# G021K.net
KiCad netlist of a schematic drawn in EAGLE
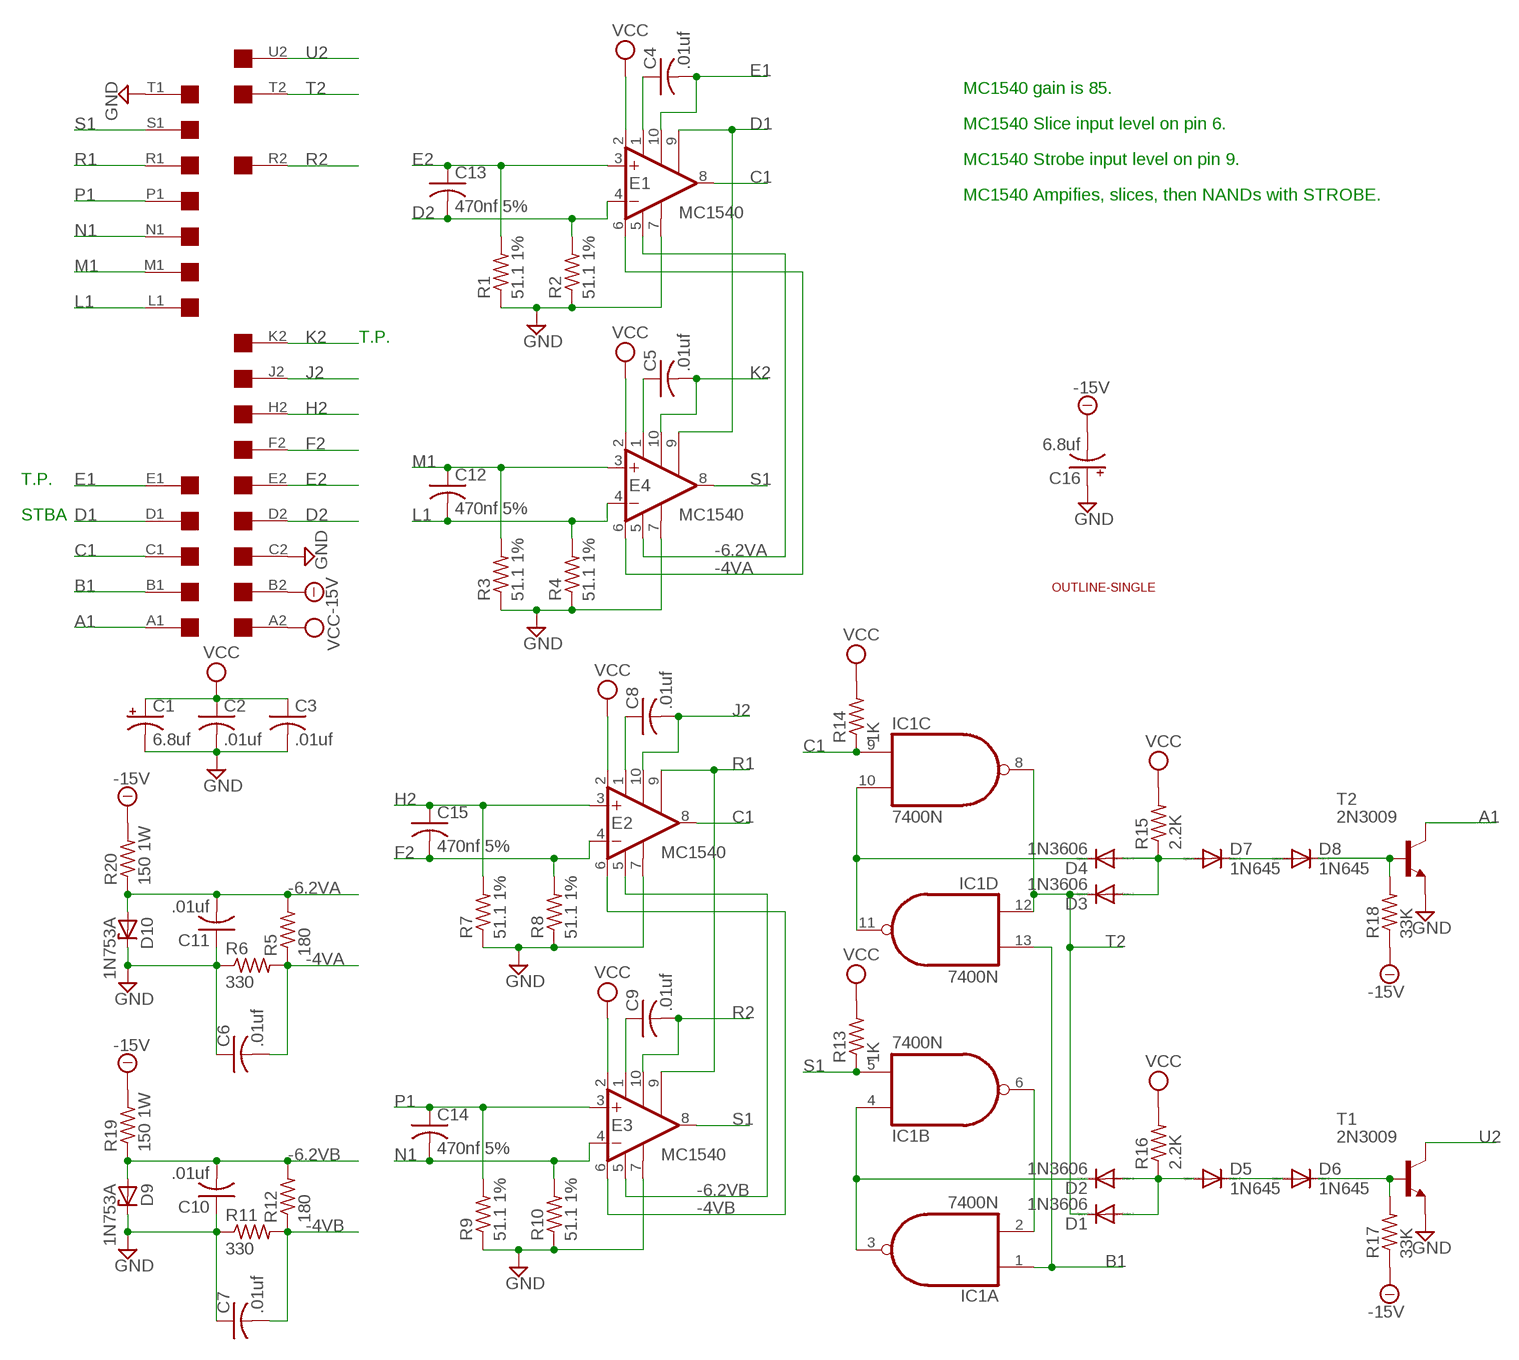
[diagram p0: schematic, sheet 1]

(export (version "E")
  (design (tool "Eeschema 10.0.6"))
  (components
    (comp (ref "C1")
      (value "6.8uf")
      (footprint "eagle-import:E22-6")
      (libsource (lib "eagle-import") (part "CPOL-USE22-6AXIAL"))
    )
    (comp (ref "C2")
      (value ".01uf")
      (footprint "eagle-import:C050-025X075")
      (libsource (lib "eagle-import") (part "C-US050-025X075"))
    )
    (comp (ref "C3")
      (value ".01uf")
      (footprint "eagle-import:C050-025X075")
      (libsource (lib "eagle-import") (part "C-US050-025X075"))
    )
    (comp (ref "C4")
      (value ".01uf")
      (footprint "eagle-import:C050-025X075")
      (libsource (lib "eagle-import") (part "C-US050-025X075"))
    )
    (comp (ref "C5")
      (value ".01uf")
      (footprint "eagle-import:C050-025X075")
      (libsource (lib "eagle-import") (part "C-US050-025X075"))
    )
    (comp (ref "C6")
      (value ".01uf")
      (footprint "eagle-import:C050-025X075")
      (libsource (lib "eagle-import") (part "C-US050-025X075"))
    )
    (comp (ref "C7")
      (value ".01uf")
      (footprint "eagle-import:C050-025X075")
      (libsource (lib "eagle-import") (part "C-US050-025X075"))
    )
    (comp (ref "C8")
      (value ".01uf")
      (footprint "eagle-import:C050-025X075")
      (libsource (lib "eagle-import") (part "C-US050-025X075"))
    )
    (comp (ref "C9")
      (value ".01uf")
      (footprint "eagle-import:C050-025X075")
      (libsource (lib "eagle-import") (part "C-US050-025X075"))
    )
    (comp (ref "C10")
      (value ".01uf")
      (footprint "eagle-import:C050-025X075")
      (libsource (lib "eagle-import") (part "C-US050-025X075"))
    )
    (comp (ref "C11")
      (value ".01uf")
      (footprint "eagle-import:C050-025X075")
      (libsource (lib "eagle-import") (part "C-US050-025X075"))
    )
    (comp (ref "C12")
      (value "470nf 5%")
      (footprint "eagle-import:C050-025X075")
      (libsource (lib "eagle-import") (part "C-US050-025X075"))
    )
    (comp (ref "C13")
      (value "470nf 5%")
      (footprint "eagle-import:C050-025X075")
      (libsource (lib "eagle-import") (part "C-US050-025X075"))
    )
    (comp (ref "C14")
      (value "470nf 5%")
      (footprint "eagle-import:C050-025X075")
      (libsource (lib "eagle-import") (part "C-US050-025X075"))
    )
    (comp (ref "C15")
      (value "470nf 5%")
      (footprint "eagle-import:C050-025X075")
      (libsource (lib "eagle-import") (part "C-US050-025X075"))
    )
    (comp (ref "C16")
      (value "6.8uf")
      (footprint "eagle-import:E22-6")
      (libsource (lib "eagle-import") (part "CPOL-USE22-6AXIAL"))
    )
    (comp (ref "D1")
      (value "1N3606")
      (footprint "eagle-import:DO35-10")
      (libsource (lib "eagle-import") (part "1N4148DO35-10"))
    )
    (comp (ref "D2")
      (value "1N3606")
      (footprint "eagle-import:DO35-10")
      (libsource (lib "eagle-import") (part "1N4148DO35-10"))
    )
    (comp (ref "D3")
      (value "1N3606")
      (footprint "eagle-import:DO35-10")
      (libsource (lib "eagle-import") (part "1N4148DO35-10"))
    )
    (comp (ref "D4")
      (value "1N3606")
      (footprint "eagle-import:DO35-10")
      (libsource (lib "eagle-import") (part "1N4148DO35-10"))
    )
    (comp (ref "D5")
      (value "1N645")
      (footprint "eagle-import:DO35-10")
      (libsource (lib "eagle-import") (part "1N4148DO35-10"))
    )
    (comp (ref "D6")
      (value "1N645")
      (footprint "eagle-import:DO35-10")
      (libsource (lib "eagle-import") (part "1N4148DO35-10"))
    )
    (comp (ref "D7")
      (value "1N645")
      (footprint "eagle-import:DO35-10")
      (libsource (lib "eagle-import") (part "1N4148DO35-10"))
    )
    (comp (ref "D8")
      (value "1N645")
      (footprint "eagle-import:DO35-10")
      (libsource (lib "eagle-import") (part "1N4148DO35-10"))
    )
    (comp (ref "D9")
      (value "1N753A")
      (footprint "eagle-import:F126Z10")
      (libsource (lib "eagle-import") (part "ZENER-DIODEF126-10"))
    )
    (comp (ref "D10")
      (value "1N753A")
      (footprint "eagle-import:F126Z10")
      (libsource (lib "eagle-import") (part "ZENER-DIODEF126-10"))
    )
    (comp (ref "E1")
      (value "MC1540")
      (footprint "eagle-import:602B")
      (libsource (lib "eagle-import") (part "MC1540G"))
    )
    (comp (ref "E2")
      (value "MC1540")
      (footprint "eagle-import:602B")
      (libsource (lib "eagle-import") (part "MC1540G"))
    )
    (comp (ref "E3")
      (value "MC1540")
      (footprint "eagle-import:602B")
      (libsource (lib "eagle-import") (part "MC1540G"))
    )
    (comp (ref "E4")
      (value "MC1540")
      (footprint "eagle-import:602B")
      (libsource (lib "eagle-import") (part "MC1540G"))
    )
    (comp (ref "IC1")
      (value "7400N")
      (footprint "eagle-import:DIL14")
      (libsource (lib "eagle-import") (part "7400N"))
    )
    (comp (ref "R1")
      (value "51.1 1%")
      (footprint "eagle-import:0207_10")
      (libsource (lib "eagle-import") (part "R-US_0207/10"))
    )
    (comp (ref "R2")
      (value "51.1 1%")
      (footprint "eagle-import:0207_10")
      (libsource (lib "eagle-import") (part "R-US_0207/10"))
    )
    (comp (ref "R3")
      (value "51.1 1%")
      (footprint "eagle-import:0207_10")
      (libsource (lib "eagle-import") (part "R-US_0207/10"))
    )
    (comp (ref "R4")
      (value "51.1 1%")
      (footprint "eagle-import:0207_10")
      (libsource (lib "eagle-import") (part "R-US_0207/10"))
    )
    (comp (ref "R5")
      (value "180")
      (footprint "eagle-import:0207_10")
      (libsource (lib "eagle-import") (part "R-US_0207/10"))
    )
    (comp (ref "R6")
      (value "330")
      (footprint "eagle-import:0207_10")
      (libsource (lib "eagle-import") (part "R-US_0207/10"))
    )
    (comp (ref "R7")
      (value "51.1 1%")
      (footprint "eagle-import:0207_10")
      (libsource (lib "eagle-import") (part "R-US_0207/10"))
    )
    (comp (ref "R8")
      (value "51.1 1%")
      (footprint "eagle-import:0207_10")
      (libsource (lib "eagle-import") (part "R-US_0207/10"))
    )
    (comp (ref "R9")
      (value "51.1 1%")
      (footprint "eagle-import:0207_10")
      (libsource (lib "eagle-import") (part "R-US_0207/10"))
    )
    (comp (ref "R10")
      (value "51.1 1%")
      (footprint "eagle-import:0207_10")
      (libsource (lib "eagle-import") (part "R-US_0207/10"))
    )
    (comp (ref "R11")
      (value "330")
      (footprint "eagle-import:0207_10")
      (libsource (lib "eagle-import") (part "R-US_0207/10"))
    )
    (comp (ref "R12")
      (value "180")
      (footprint "eagle-import:0207_10")
      (libsource (lib "eagle-import") (part "R-US_0207/10"))
    )
    (comp (ref "R13")
      (value "1K")
      (footprint "eagle-import:0207_10")
      (libsource (lib "eagle-import") (part "R-US_0207/10"))
    )
    (comp (ref "R14")
      (value "1K")
      (footprint "eagle-import:0207_10")
      (libsource (lib "eagle-import") (part "R-US_0207/10"))
    )
    (comp (ref "R15")
      (value "2.2K")
      (footprint "eagle-import:0207_10")
      (libsource (lib "eagle-import") (part "R-US_0207/10"))
    )
    (comp (ref "R16")
      (value "2.2K")
      (footprint "eagle-import:0207_10")
      (libsource (lib "eagle-import") (part "R-US_0207/10"))
    )
    (comp (ref "R17")
      (value "33K")
      (footprint "eagle-import:0207_10")
      (libsource (lib "eagle-import") (part "R-US_0207/10"))
    )
    (comp (ref "R18")
      (value "33K")
      (footprint "eagle-import:0207_10")
      (libsource (lib "eagle-import") (part "R-US_0207/10"))
    )
    (comp (ref "R19")
      (value "150 1W")
      (footprint "eagle-import:0414_15")
      (libsource (lib "eagle-import") (part "R-US_0414/15"))
    )
    (comp (ref "R20")
      (value "150 1W")
      (footprint "eagle-import:0414_15")
      (libsource (lib "eagle-import") (part "R-US_0414/15"))
    )
    (comp (ref "T1")
      (value "2N3009")
      (footprint "eagle-import:TO92")
      (libsource (lib "eagle-import") (part "2N3565"))
    )
    (comp (ref "T2")
      (value "2N3009")
      (footprint "eagle-import:TO92")
      (libsource (lib "eagle-import") (part "2N3565"))
    )
    (comp (ref "U$1")
      (value "SINGLE")
      (footprint "eagle-import:EDGE-CON2")
      (libsource (lib "eagle-import") (part "SINGLE"))
    )
    (comp (ref "U$2")
      (value "OUTLINE-SINGLE")
      (footprint "eagle-import:SINGLE")
      (libsource (lib "eagle-import") (part "OUTLINE-SINGLE"))
    )
  )
  (nets
    (net (code "1") (name "-15V") (class "Default")
      (node (ref "C16") (pin "-") (pinfunction "-_-") (pintype "passive"))
      (node (ref "R17") (pin "1") (pinfunction "1_1") (pintype "passive"))
      (node (ref "R18") (pin "1") (pinfunction "1_1") (pintype "passive"))
      (node (ref "R19") (pin "2") (pinfunction "2_2") (pintype "passive"))
      (node (ref "R20") (pin "2") (pinfunction "2_2") (pintype "passive"))
      (node (ref "U$1") (pin "B2") (pinfunction "1_B2") (pintype "bidirectional"))
    )
    (net (code "2") (name "/-4VA") (class "Default")
      (node (ref "C6") (pin "2") (pinfunction "2_2") (pintype "passive"))
      (node (ref "E1") (pin "6") (pinfunction "SLICE_6") (pintype "bidirectional"))
      (node (ref "E4") (pin "6") (pinfunction "SLICE_6") (pintype "bidirectional"))
      (node (ref "R5") (pin "1") (pinfunction "1_1") (pintype "passive"))
      (node (ref "R6") (pin "2") (pinfunction "2_2") (pintype "passive"))
    )
    (net (code "3") (name "/-4VB") (class "Default")
      (node (ref "C7") (pin "2") (pinfunction "2_2") (pintype "passive"))
      (node (ref "E2") (pin "6") (pinfunction "SLICE_6") (pintype "bidirectional"))
      (node (ref "E3") (pin "6") (pinfunction "SLICE_6") (pintype "bidirectional"))
      (node (ref "R11") (pin "2") (pinfunction "2_2") (pintype "passive"))
      (node (ref "R12") (pin "1") (pinfunction "1_1") (pintype "passive"))
    )
    (net (code "4") (name "/-6.2VA") (class "Default")
      (node (ref "C11") (pin "2") (pinfunction "2_2") (pintype "passive"))
      (node (ref "D10") (pin "A") (pinfunction "A_A") (pintype "passive"))
      (node (ref "E1") (pin "5") (pinfunction "V-_5") (pintype "power_in"))
      (node (ref "E4") (pin "5") (pinfunction "V-_5") (pintype "power_in"))
      (node (ref "R20") (pin "1") (pinfunction "1_1") (pintype "passive"))
      (node (ref "R5") (pin "2") (pinfunction "2_2") (pintype "passive"))
    )
    (net (code "5") (name "/-6.2VB") (class "Default")
      (node (ref "C10") (pin "2") (pinfunction "2_2") (pintype "passive"))
      (node (ref "D9") (pin "A") (pinfunction "A_A") (pintype "passive"))
      (node (ref "E2") (pin "5") (pinfunction "V-_5") (pintype "power_in"))
      (node (ref "E3") (pin "5") (pinfunction "V-_5") (pintype "power_in"))
      (node (ref "R12") (pin "2") (pinfunction "2_2") (pintype "passive"))
      (node (ref "R19") (pin "1") (pinfunction "1_1") (pintype "passive"))
    )
    (net (code "6") (name "/A1") (class "Default")
      (node (ref "T2") (pin "1") (pinfunction "C_1") (pintype "passive"))
      (node (ref "U$1") (pin "A1") (pinfunction "1_A1") (pintype "bidirectional"))
    )
    (net (code "7") (name "/B1") (class "Default")
      (node (ref "IC1") (pin "1") (pinfunction "I0_1") (pintype "input"))
      (node (ref "IC1") (pin "13") (pinfunction "I1_13") (pintype "input"))
      (node (ref "U$1") (pin "B1") (pinfunction "1_B1") (pintype "bidirectional"))
    )
    (net (code "8") (name "/C1") (class "Default")
      (node (ref "E1") (pin "8") (pinfunction "OUT_8") (pintype "open_collector"))
      (node (ref "E2") (pin "8") (pinfunction "OUT_8") (pintype "open_collector"))
      (node (ref "IC1") (pin "9") (pinfunction "I0_9") (pintype "input"))
      (node (ref "R14") (pin "1") (pinfunction "1_1") (pintype "passive"))
      (node (ref "U$1") (pin "C1") (pinfunction "1_C1") (pintype "bidirectional"))
    )
    (net (code "9") (name "/D1") (class "Default")
      (node (ref "E1") (pin "9") (pinfunction "ISTROBE_9") (pintype "passive"))
      (node (ref "E4") (pin "9") (pinfunction "ISTROBE_9") (pintype "passive"))
      (node (ref "U$1") (pin "D1") (pinfunction "1_D1") (pintype "bidirectional"))
    )
    (net (code "10") (name "/D2") (class "Default")
      (node (ref "C13") (pin "2") (pinfunction "2_2") (pintype "passive"))
      (node (ref "E1") (pin "4") (pinfunction "-IN_4") (pintype "input"))
      (node (ref "R2") (pin "2") (pinfunction "2_2") (pintype "passive"))
      (node (ref "U$1") (pin "D2") (pinfunction "1_D2") (pintype "bidirectional"))
    )
    (net (code "11") (name "/E1") (class "Default")
      (node (ref "C4") (pin "2") (pinfunction "2_2") (pintype "passive"))
      (node (ref "E1") (pin "10") (pinfunction "CEXTB_10") (pintype "passive"))
      (node (ref "U$1") (pin "E1") (pinfunction "1_E1") (pintype "bidirectional"))
    )
    (net (code "12") (name "/E2") (class "Default")
      (node (ref "C13") (pin "1") (pinfunction "1_1") (pintype "passive"))
      (node (ref "E1") (pin "3") (pinfunction "+IN_3") (pintype "input"))
      (node (ref "R1") (pin "2") (pinfunction "2_2") (pintype "passive"))
      (node (ref "U$1") (pin "E2") (pinfunction "1_E2") (pintype "bidirectional"))
    )
    (net (code "13") (name "/F2") (class "Default")
      (node (ref "C15") (pin "2") (pinfunction "2_2") (pintype "passive"))
      (node (ref "E2") (pin "4") (pinfunction "-IN_4") (pintype "input"))
      (node (ref "R8") (pin "2") (pinfunction "2_2") (pintype "passive"))
      (node (ref "U$1") (pin "F2") (pinfunction "1_F2") (pintype "bidirectional"))
    )
    (net (code "14") (name "/H2") (class "Default")
      (node (ref "C15") (pin "1") (pinfunction "1_1") (pintype "passive"))
      (node (ref "E2") (pin "3") (pinfunction "+IN_3") (pintype "input"))
      (node (ref "R7") (pin "2") (pinfunction "2_2") (pintype "passive"))
      (node (ref "U$1") (pin "H2") (pinfunction "1_H2") (pintype "bidirectional"))
    )
    (net (code "15") (name "/J2") (class "Default")
      (node (ref "C8") (pin "2") (pinfunction "2_2") (pintype "passive"))
      (node (ref "E2") (pin "10") (pinfunction "CEXTB_10") (pintype "passive"))
      (node (ref "U$1") (pin "J2") (pinfunction "1_J2") (pintype "bidirectional"))
    )
    (net (code "16") (name "/K2") (class "Default")
      (node (ref "C5") (pin "2") (pinfunction "2_2") (pintype "passive"))
      (node (ref "E4") (pin "10") (pinfunction "CEXTB_10") (pintype "passive"))
      (node (ref "U$1") (pin "K2") (pinfunction "1_K2") (pintype "bidirectional"))
    )
    (net (code "17") (name "/L1") (class "Default")
      (node (ref "C12") (pin "2") (pinfunction "2_2") (pintype "passive"))
      (node (ref "E4") (pin "4") (pinfunction "-IN_4") (pintype "input"))
      (node (ref "R4") (pin "2") (pinfunction "2_2") (pintype "passive"))
      (node (ref "U$1") (pin "L1") (pinfunction "1_L1") (pintype "bidirectional"))
    )
    (net (code "18") (name "/M1") (class "Default")
      (node (ref "C12") (pin "1") (pinfunction "1_1") (pintype "passive"))
      (node (ref "E4") (pin "3") (pinfunction "+IN_3") (pintype "input"))
      (node (ref "R3") (pin "2") (pinfunction "2_2") (pintype "passive"))
      (node (ref "U$1") (pin "M1") (pinfunction "1_M1") (pintype "bidirectional"))
    )
    (net (code "19") (name "/N1") (class "Default")
      (node (ref "C14") (pin "2") (pinfunction "2_2") (pintype "passive"))
      (node (ref "E3") (pin "4") (pinfunction "-IN_4") (pintype "input"))
      (node (ref "R10") (pin "2") (pinfunction "2_2") (pintype "passive"))
      (node (ref "U$1") (pin "N1") (pinfunction "1_N1") (pintype "bidirectional"))
    )
    (net (code "20") (name "/P1") (class "Default")
      (node (ref "C14") (pin "1") (pinfunction "1_1") (pintype "passive"))
      (node (ref "E3") (pin "3") (pinfunction "+IN_3") (pintype "input"))
      (node (ref "R9") (pin "2") (pinfunction "2_2") (pintype "passive"))
      (node (ref "U$1") (pin "P1") (pinfunction "1_P1") (pintype "bidirectional"))
    )
    (net (code "21") (name "/R1") (class "Default")
      (node (ref "E2") (pin "9") (pinfunction "ISTROBE_9") (pintype "passive"))
      (node (ref "E3") (pin "9") (pinfunction "ISTROBE_9") (pintype "passive"))
      (node (ref "U$1") (pin "R1") (pinfunction "1_R1") (pintype "bidirectional"))
    )
    (net (code "22") (name "/R2") (class "Default")
      (node (ref "C9") (pin "2") (pinfunction "2_2") (pintype "passive"))
      (node (ref "E3") (pin "10") (pinfunction "CEXTB_10") (pintype "passive"))
      (node (ref "U$1") (pin "R2") (pinfunction "1_R2") (pintype "bidirectional"))
    )
    (net (code "23") (name "/S1") (class "Default")
      (node (ref "E3") (pin "8") (pinfunction "OUT_8") (pintype "open_collector"))
      (node (ref "E4") (pin "8") (pinfunction "OUT_8") (pintype "open_collector"))
      (node (ref "IC1") (pin "5") (pinfunction "I1_5") (pintype "input"))
      (node (ref "R13") (pin "1") (pinfunction "1_1") (pintype "passive"))
      (node (ref "U$1") (pin "S1") (pinfunction "1_S1") (pintype "bidirectional"))
    )
    (net (code "24") (name "/T2") (class "Default")
      (node (ref "D1") (pin "C") (pinfunction "C_C") (pintype "passive"))
      (node (ref "D3") (pin "C") (pinfunction "C_C") (pintype "passive"))
      (node (ref "IC1") (pin "12") (pinfunction "I0_12") (pintype "input"))
      (node (ref "IC1") (pin "8") (pinfunction "O_8") (pintype "output"))
      (node (ref "U$1") (pin "T2") (pinfunction "1_T2") (pintype "bidirectional"))
    )
    (net (code "25") (name "/U2") (class "Default")
      (node (ref "T1") (pin "1") (pinfunction "C_1") (pintype "passive"))
      (node (ref "U$1") (pin "U2") (pinfunction "1_U2") (pintype "bidirectional"))
    )
    (net (code "26") (name "GND") (class "Default")
      (node (ref "C1") (pin "-") (pinfunction "-_-") (pintype "passive"))
      (node (ref "C10") (pin "1") (pinfunction "1_1") (pintype "passive"))
      (node (ref "C11") (pin "1") (pinfunction "1_1") (pintype "passive"))
      (node (ref "C16") (pin "+") (pinfunction "+_+") (pintype "passive"))
      (node (ref "C2") (pin "2") (pinfunction "2_2") (pintype "passive"))
      (node (ref "C3") (pin "2") (pinfunction "2_2") (pintype "passive"))
      (node (ref "C6") (pin "1") (pinfunction "1_1") (pintype "passive"))
      (node (ref "C7") (pin "1") (pinfunction "1_1") (pintype "passive"))
      (node (ref "D10") (pin "C") (pinfunction "C_C") (pintype "passive"))
      (node (ref "D9") (pin "C") (pinfunction "C_C") (pintype "passive"))
      (node (ref "E1") (pin "7") (pinfunction "GND_7") (pintype "power_in"))
      (node (ref "E2") (pin "7") (pinfunction "GND_7") (pintype "power_in"))
      (node (ref "E3") (pin "7") (pinfunction "GND_7") (pintype "power_in"))
      (node (ref "E4") (pin "7") (pinfunction "GND_7") (pintype "power_in"))
      (node (ref "R1") (pin "1") (pinfunction "1_1") (pintype "passive"))
      (node (ref "R10") (pin "1") (pinfunction "1_1") (pintype "passive"))
      (node (ref "R11") (pin "1") (pinfunction "1_1") (pintype "passive"))
      (node (ref "R2") (pin "1") (pinfunction "1_1") (pintype "passive"))
      (node (ref "R3") (pin "1") (pinfunction "1_1") (pintype "passive"))
      (node (ref "R4") (pin "1") (pinfunction "1_1") (pintype "passive"))
      (node (ref "R6") (pin "1") (pinfunction "1_1") (pintype "passive"))
      (node (ref "R7") (pin "1") (pinfunction "1_1") (pintype "passive"))
      (node (ref "R8") (pin "1") (pinfunction "1_1") (pintype "passive"))
      (node (ref "R9") (pin "1") (pinfunction "1_1") (pintype "passive"))
      (node (ref "T1") (pin "3") (pinfunction "E_3") (pintype "passive"))
      (node (ref "T2") (pin "3") (pinfunction "E_3") (pintype "passive"))
      (node (ref "U$1") (pin "C2") (pinfunction "1_C2") (pintype "bidirectional"))
      (node (ref "U$1") (pin "T1") (pinfunction "1_T1") (pintype "bidirectional"))
    )
    (net (code "27") (name "Net-(D1-PadA)") (class "Default")
      (node (ref "D1") (pin "A") (pinfunction "A_A") (pintype "passive"))
      (node (ref "D2") (pin "A") (pinfunction "A_A") (pintype "passive"))
      (node (ref "D5") (pin "A") (pinfunction "A_A") (pintype "passive"))
      (node (ref "R16") (pin "1") (pinfunction "1_1") (pintype "passive"))
    )
    (net (code "28") (name "Net-(D3-PadA)") (class "Default")
      (node (ref "D3") (pin "A") (pinfunction "A_A") (pintype "passive"))
      (node (ref "D4") (pin "A") (pinfunction "A_A") (pintype "passive"))
      (node (ref "D7") (pin "A") (pinfunction "A_A") (pintype "passive"))
      (node (ref "R15") (pin "1") (pinfunction "1_1") (pintype "passive"))
    )
    (net (code "29") (name "Net-(D5-PadC)") (class "Default")
      (node (ref "D5") (pin "C") (pinfunction "C_C") (pintype "passive"))
      (node (ref "D6") (pin "A") (pinfunction "A_A") (pintype "passive"))
    )
    (net (code "30") (name "Net-(D7-PadC)") (class "Default")
      (node (ref "D7") (pin "C") (pinfunction "C_C") (pintype "passive"))
      (node (ref "D8") (pin "A") (pinfunction "A_A") (pintype "passive"))
    )
    (net (code "31") (name "Net-(E1-CEXTA)") (class "Default")
      (node (ref "C4") (pin "1") (pinfunction "1_1") (pintype "passive"))
      (node (ref "E1") (pin "1") (pinfunction "CEXTA_1") (pintype "passive"))
    )
    (net (code "32") (name "Net-(E2-CEXTA)") (class "Default")
      (node (ref "C8") (pin "1") (pinfunction "1_1") (pintype "passive"))
      (node (ref "E2") (pin "1") (pinfunction "CEXTA_1") (pintype "passive"))
    )
    (net (code "33") (name "Net-(E3-CEXTA)") (class "Default")
      (node (ref "C9") (pin "1") (pinfunction "1_1") (pintype "passive"))
      (node (ref "E3") (pin "1") (pinfunction "CEXTA_1") (pintype "passive"))
    )
    (net (code "34") (name "Net-(E4-CEXTA)") (class "Default")
      (node (ref "C5") (pin "1") (pinfunction "1_1") (pintype "passive"))
      (node (ref "E4") (pin "1") (pinfunction "CEXTA_1") (pintype "passive"))
    )
    (net (code "35") (name "Net-(IC1A-I1)") (class "Default")
      (node (ref "IC1") (pin "2") (pinfunction "I1_2") (pintype "input"))
      (node (ref "IC1") (pin "6") (pinfunction "O_6") (pintype "output"))
    )
    (net (code "36") (name "Net-(IC1A-O)") (class "Default")
      (node (ref "D2") (pin "C") (pinfunction "C_C") (pintype "passive"))
      (node (ref "IC1") (pin "3") (pinfunction "O_3") (pintype "output"))
      (node (ref "IC1") (pin "4") (pinfunction "I0_4") (pintype "input"))
    )
    (net (code "37") (name "Net-(IC1C-I1)") (class "Default")
      (node (ref "D4") (pin "C") (pinfunction "C_C") (pintype "passive"))
      (node (ref "IC1") (pin "10") (pinfunction "I1_10") (pintype "input"))
      (node (ref "IC1") (pin "11") (pinfunction "O_11") (pintype "output"))
    )
    (net (code "38") (name "Net-(T1-B)") (class "Default")
      (node (ref "D6") (pin "C") (pinfunction "C_C") (pintype "passive"))
      (node (ref "R17") (pin "2") (pinfunction "2_2") (pintype "passive"))
      (node (ref "T1") (pin "2") (pinfunction "B_2") (pintype "passive"))
    )
    (net (code "39") (name "Net-(T2-B)") (class "Default")
      (node (ref "D8") (pin "C") (pinfunction "C_C") (pintype "passive"))
      (node (ref "R18") (pin "2") (pinfunction "2_2") (pintype "passive"))
      (node (ref "T2") (pin "2") (pinfunction "B_2") (pintype "passive"))
    )
    (net (code "40") (name "VCC") (class "Default")
      (node (ref "C1") (pin "+") (pinfunction "+_+") (pintype "passive"))
      (node (ref "C2") (pin "1") (pinfunction "1_1") (pintype "passive"))
      (node (ref "C3") (pin "1") (pinfunction "1_1") (pintype "passive"))
      (node (ref "E1") (pin "2") (pinfunction "V+_2") (pintype "power_in"))
      (node (ref "E2") (pin "2") (pinfunction "V+_2") (pintype "power_in"))
      (node (ref "E3") (pin "2") (pinfunction "V+_2") (pintype "power_in"))
      (node (ref "E4") (pin "2") (pinfunction "V+_2") (pintype "power_in"))
      (node (ref "R13") (pin "2") (pinfunction "2_2") (pintype "passive"))
      (node (ref "R14") (pin "2") (pinfunction "2_2") (pintype "passive"))
      (node (ref "R15") (pin "2") (pinfunction "2_2") (pintype "passive"))
      (node (ref "R16") (pin "2") (pinfunction "2_2") (pintype "passive"))
      (node (ref "U$1") (pin "A2") (pinfunction "1_A2") (pintype "bidirectional"))
    )
  )
)
